# M116X.net
KiCad netlist of a schematic drawn in EAGLE
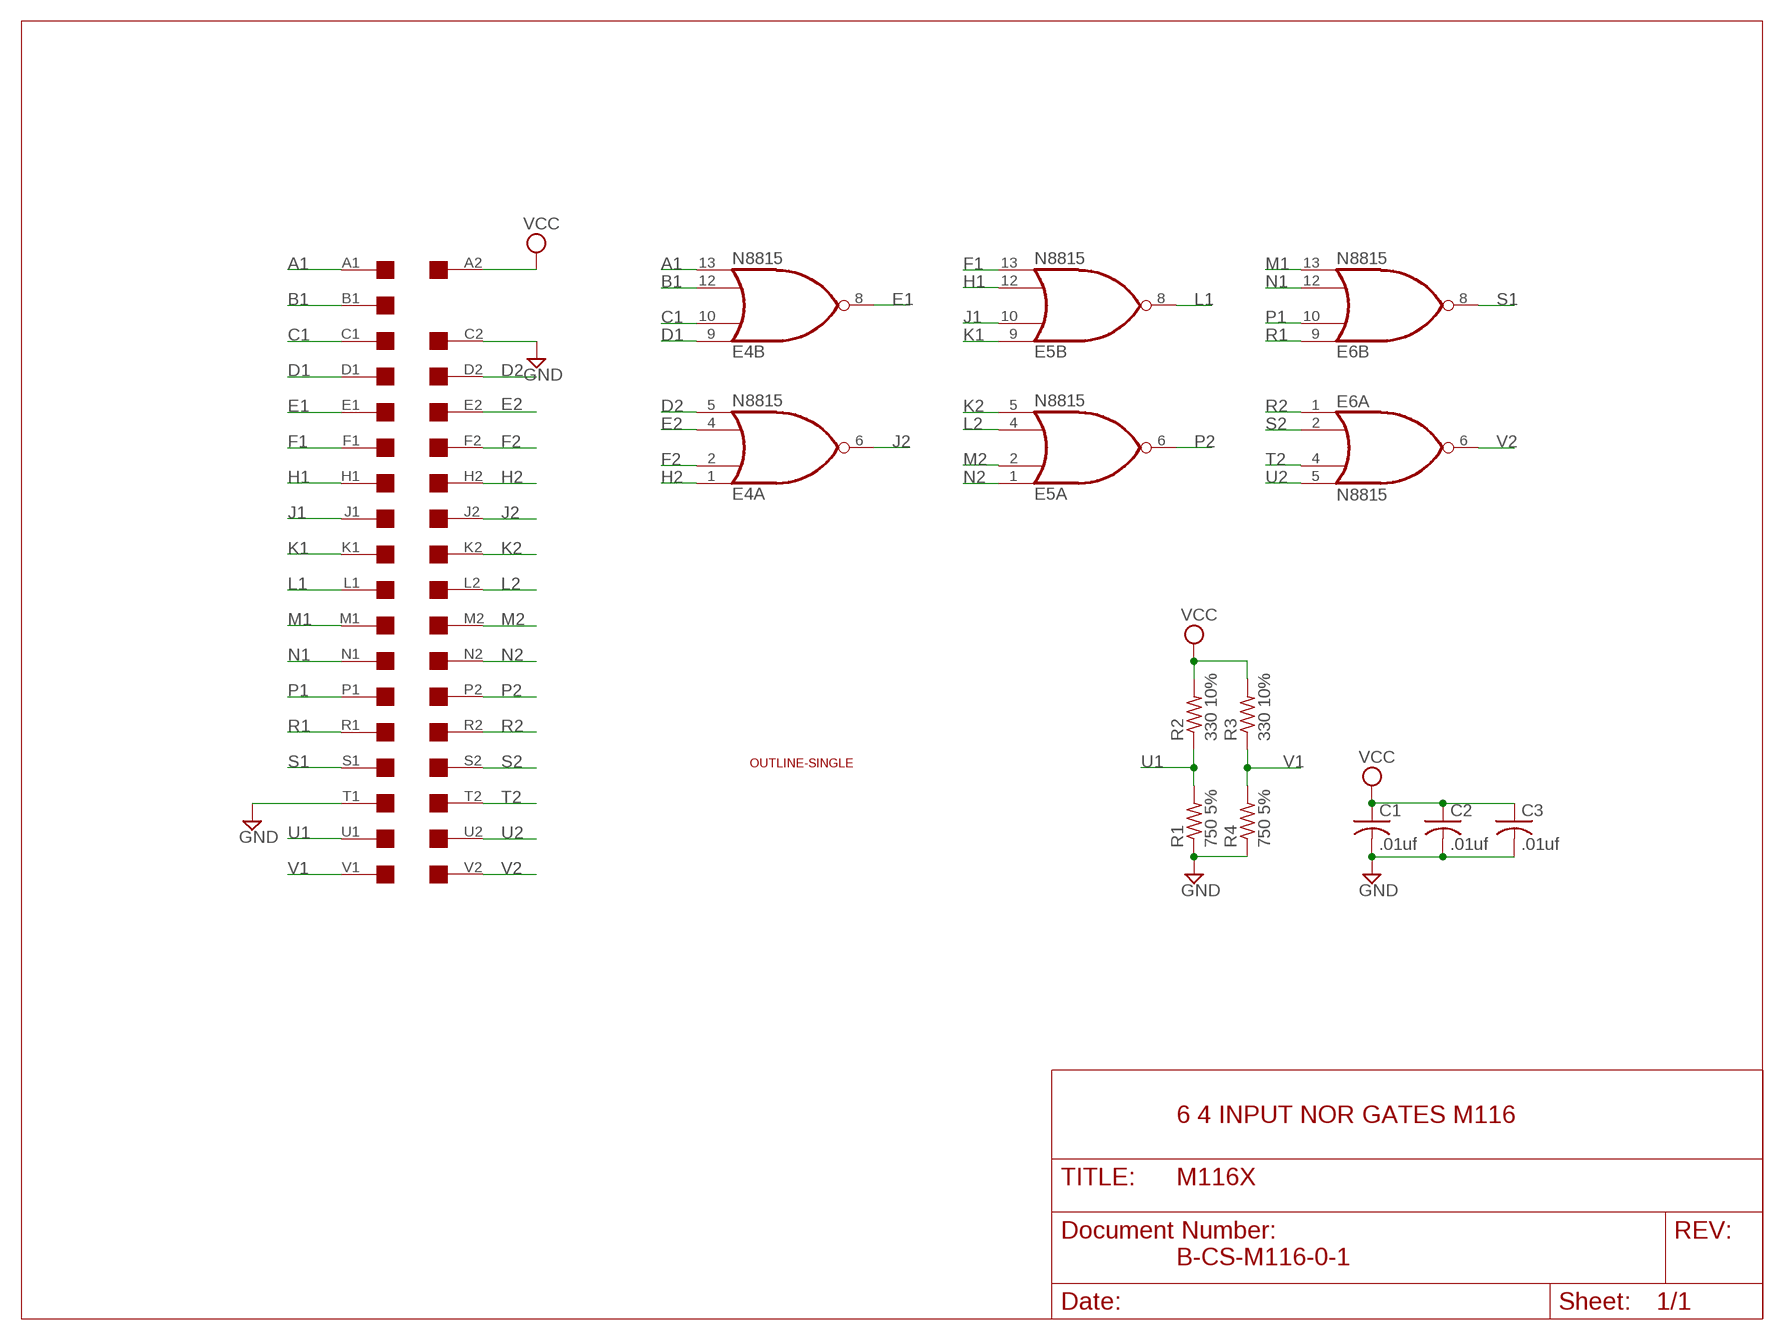
[diagram p0: schematic, sheet 1]

(export (version "E")
  (design (tool "Eeschema 10.0.6"))
  (components
    (comp (ref "C1")
      (value ".01uf")
      (footprint "eagle-import:C050-025X075")
      (libsource (lib "eagle-import") (part "C-US050-025X075"))
    )
    (comp (ref "C2")
      (value ".01uf")
      (footprint "eagle-import:C050-025X075")
      (libsource (lib "eagle-import") (part "C-US050-025X075"))
    )
    (comp (ref "C3")
      (value ".01uf")
      (footprint "eagle-import:C050-025X075")
      (libsource (lib "eagle-import") (part "C-US050-025X075"))
    )
    (comp (ref "E4")
      (value "N8815")
      (footprint "eagle-import:DIL14")
      (libsource (lib "eagle-import") (part "N8815"))
    )
    (comp (ref "E5")
      (value "N8815")
      (footprint "eagle-import:DIL14")
      (libsource (lib "eagle-import") (part "N8815"))
    )
    (comp (ref "E6")
      (value "N8815")
      (footprint "eagle-import:DIL14")
      (libsource (lib "eagle-import") (part "N8815"))
    )
    (comp (ref "R1")
      (value "750 5%")
      (footprint "eagle-import:0207_10")
      (libsource (lib "eagle-import") (part "R-US_0207/10"))
    )
    (comp (ref "R2")
      (value "330 10%")
      (footprint "eagle-import:0207_10")
      (libsource (lib "eagle-import") (part "R-US_0207/10"))
    )
    (comp (ref "R3")
      (value "330 10%")
      (footprint "eagle-import:0207_10")
      (libsource (lib "eagle-import") (part "R-US_0207/10"))
    )
    (comp (ref "R4")
      (value "750 5%")
      (footprint "eagle-import:0207_10")
      (libsource (lib "eagle-import") (part "R-US_0207/10"))
    )
    (comp (ref "U$1")
      (value "SINGLE")
      (footprint "eagle-import:EDGE-CON2")
      (libsource (lib "eagle-import") (part "SINGLE"))
    )
    (comp (ref "U$4")
      (value "OUTLINE-SINGLE")
      (footprint "eagle-import:SINGLE")
      (libsource (lib "eagle-import") (part "OUTLINE-SINGLE"))
    )
  )
  (nets
    (net (code "1") (name "/A1") (class "Default")
      (node (ref "E4") (pin "13") (pinfunction "I3_13") (pintype "input"))
      (node (ref "U$1") (pin "A1") (pinfunction "1_A1") (pintype "bidirectional"))
    )
    (net (code "2") (name "/B1") (class "Default")
      (node (ref "E4") (pin "12") (pinfunction "I2_12") (pintype "input"))
      (node (ref "U$1") (pin "B1") (pinfunction "1_B1") (pintype "bidirectional"))
    )
    (net (code "3") (name "/C1") (class "Default")
      (node (ref "E4") (pin "10") (pinfunction "I1_10") (pintype "input"))
      (node (ref "U$1") (pin "C1") (pinfunction "1_C1") (pintype "bidirectional"))
    )
    (net (code "4") (name "/D1") (class "Default")
      (node (ref "E4") (pin "9") (pinfunction "I0_9") (pintype "input"))
      (node (ref "U$1") (pin "D1") (pinfunction "1_D1") (pintype "bidirectional"))
    )
    (net (code "5") (name "/D2") (class "Default")
      (node (ref "E4") (pin "5") (pinfunction "I3_5") (pintype "input"))
      (node (ref "U$1") (pin "D2") (pinfunction "1_D2") (pintype "bidirectional"))
    )
    (net (code "6") (name "/E1") (class "Default")
      (node (ref "E4") (pin "8") (pinfunction "O_8") (pintype "output"))
      (node (ref "U$1") (pin "E1") (pinfunction "1_E1") (pintype "bidirectional"))
    )
    (net (code "7") (name "/E2") (class "Default")
      (node (ref "E4") (pin "4") (pinfunction "I2_4") (pintype "input"))
      (node (ref "U$1") (pin "E2") (pinfunction "1_E2") (pintype "bidirectional"))
    )
    (net (code "8") (name "/F1") (class "Default")
      (node (ref "E5") (pin "13") (pinfunction "I3_13") (pintype "input"))
      (node (ref "U$1") (pin "F1") (pinfunction "1_F1") (pintype "bidirectional"))
    )
    (net (code "9") (name "/F2") (class "Default")
      (node (ref "E4") (pin "2") (pinfunction "I1_2") (pintype "input"))
      (node (ref "U$1") (pin "F2") (pinfunction "1_F2") (pintype "bidirectional"))
    )
    (net (code "10") (name "/H1") (class "Default")
      (node (ref "E5") (pin "12") (pinfunction "I2_12") (pintype "input"))
      (node (ref "U$1") (pin "H1") (pinfunction "1_H1") (pintype "bidirectional"))
    )
    (net (code "11") (name "/H2") (class "Default")
      (node (ref "E4") (pin "1") (pinfunction "I0_1") (pintype "input"))
      (node (ref "U$1") (pin "H2") (pinfunction "1_H2") (pintype "bidirectional"))
    )
    (net (code "12") (name "/J1") (class "Default")
      (node (ref "E5") (pin "10") (pinfunction "I1_10") (pintype "input"))
      (node (ref "U$1") (pin "J1") (pinfunction "1_J1") (pintype "bidirectional"))
    )
    (net (code "13") (name "/J2") (class "Default")
      (node (ref "E4") (pin "6") (pinfunction "O_6") (pintype "output"))
      (node (ref "U$1") (pin "J2") (pinfunction "1_J2") (pintype "bidirectional"))
    )
    (net (code "14") (name "/K1") (class "Default")
      (node (ref "E5") (pin "9") (pinfunction "I0_9") (pintype "input"))
      (node (ref "U$1") (pin "K1") (pinfunction "1_K1") (pintype "bidirectional"))
    )
    (net (code "15") (name "/K2") (class "Default")
      (node (ref "E5") (pin "5") (pinfunction "I3_5") (pintype "input"))
      (node (ref "U$1") (pin "K2") (pinfunction "1_K2") (pintype "bidirectional"))
    )
    (net (code "16") (name "/L1") (class "Default")
      (node (ref "E5") (pin "8") (pinfunction "O_8") (pintype "output"))
      (node (ref "U$1") (pin "L1") (pinfunction "1_L1") (pintype "bidirectional"))
    )
    (net (code "17") (name "/L2") (class "Default")
      (node (ref "E5") (pin "4") (pinfunction "I2_4") (pintype "input"))
      (node (ref "U$1") (pin "L2") (pinfunction "1_L2") (pintype "bidirectional"))
    )
    (net (code "18") (name "/M1") (class "Default")
      (node (ref "E6") (pin "13") (pinfunction "I3_13") (pintype "input"))
      (node (ref "U$1") (pin "M1") (pinfunction "1_M1") (pintype "bidirectional"))
    )
    (net (code "19") (name "/M2") (class "Default")
      (node (ref "E5") (pin "2") (pinfunction "I1_2") (pintype "input"))
      (node (ref "U$1") (pin "M2") (pinfunction "1_M2") (pintype "bidirectional"))
    )
    (net (code "20") (name "/N1") (class "Default")
      (node (ref "E6") (pin "12") (pinfunction "I2_12") (pintype "input"))
      (node (ref "U$1") (pin "N1") (pinfunction "1_N1") (pintype "bidirectional"))
    )
    (net (code "21") (name "/N2") (class "Default")
      (node (ref "E5") (pin "1") (pinfunction "I0_1") (pintype "input"))
      (node (ref "U$1") (pin "N2") (pinfunction "1_N2") (pintype "bidirectional"))
    )
    (net (code "22") (name "/P1") (class "Default")
      (node (ref "E6") (pin "10") (pinfunction "I1_10") (pintype "input"))
      (node (ref "U$1") (pin "P1") (pinfunction "1_P1") (pintype "bidirectional"))
    )
    (net (code "23") (name "/P2") (class "Default")
      (node (ref "E5") (pin "6") (pinfunction "O_6") (pintype "output"))
      (node (ref "U$1") (pin "P2") (pinfunction "1_P2") (pintype "bidirectional"))
    )
    (net (code "24") (name "/R1") (class "Default")
      (node (ref "E6") (pin "9") (pinfunction "I0_9") (pintype "input"))
      (node (ref "U$1") (pin "R1") (pinfunction "1_R1") (pintype "bidirectional"))
    )
    (net (code "25") (name "/R2") (class "Default")
      (node (ref "E6") (pin "1") (pinfunction "I0_1") (pintype "input"))
      (node (ref "U$1") (pin "R2") (pinfunction "1_R2") (pintype "bidirectional"))
    )
    (net (code "26") (name "/S1") (class "Default")
      (node (ref "E6") (pin "8") (pinfunction "O_8") (pintype "output"))
      (node (ref "U$1") (pin "S1") (pinfunction "1_S1") (pintype "bidirectional"))
    )
    (net (code "27") (name "/S2") (class "Default")
      (node (ref "E6") (pin "2") (pinfunction "I1_2") (pintype "input"))
      (node (ref "U$1") (pin "S2") (pinfunction "1_S2") (pintype "bidirectional"))
    )
    (net (code "28") (name "/T2") (class "Default")
      (node (ref "E6") (pin "4") (pinfunction "I2_4") (pintype "input"))
      (node (ref "U$1") (pin "T2") (pinfunction "1_T2") (pintype "bidirectional"))
    )
    (net (code "29") (name "/U1") (class "Default")
      (node (ref "R1") (pin "2") (pinfunction "2_2") (pintype "passive"))
      (node (ref "R2") (pin "1") (pinfunction "1_1") (pintype "passive"))
      (node (ref "U$1") (pin "U1") (pinfunction "1_U1") (pintype "bidirectional"))
    )
    (net (code "30") (name "/U2") (class "Default")
      (node (ref "E6") (pin "5") (pinfunction "I3_5") (pintype "input"))
      (node (ref "U$1") (pin "U2") (pinfunction "1_U2") (pintype "bidirectional"))
    )
    (net (code "31") (name "/V1") (class "Default")
      (node (ref "R3") (pin "1") (pinfunction "1_1") (pintype "passive"))
      (node (ref "R4") (pin "2") (pinfunction "2_2") (pintype "passive"))
      (node (ref "U$1") (pin "V1") (pinfunction "1_V1") (pintype "bidirectional"))
    )
    (net (code "32") (name "/V2") (class "Default")
      (node (ref "E6") (pin "6") (pinfunction "O_6") (pintype "output"))
      (node (ref "U$1") (pin "V2") (pinfunction "1_V2") (pintype "bidirectional"))
    )
    (net (code "33") (name "GND") (class "Default")
      (node (ref "C1") (pin "2") (pinfunction "2_2") (pintype "passive"))
      (node (ref "C2") (pin "2") (pinfunction "2_2") (pintype "passive"))
      (node (ref "C3") (pin "2") (pinfunction "2_2") (pintype "passive"))
      (node (ref "R1") (pin "1") (pinfunction "1_1") (pintype "passive"))
      (node (ref "R4") (pin "1") (pinfunction "1_1") (pintype "passive"))
      (node (ref "U$1") (pin "C2") (pinfunction "1_C2") (pintype "bidirectional"))
      (node (ref "U$1") (pin "T1") (pinfunction "1_T1") (pintype "bidirectional"))
    )
    (net (code "34") (name "VCC") (class "Default")
      (node (ref "C1") (pin "1") (pinfunction "1_1") (pintype "passive"))
      (node (ref "C2") (pin "1") (pinfunction "1_1") (pintype "passive"))
      (node (ref "C3") (pin "1") (pinfunction "1_1") (pintype "passive"))
      (node (ref "R2") (pin "2") (pinfunction "2_2") (pintype "passive"))
      (node (ref "R3") (pin "2") (pinfunction "2_2") (pintype "passive"))
      (node (ref "U$1") (pin "A2") (pinfunction "1_A2") (pintype "bidirectional"))
    )
  )
)
